# OpenPLCv0_2_0_SDCard.net
KiCad netlist of a schematic drawn in Altium Designer
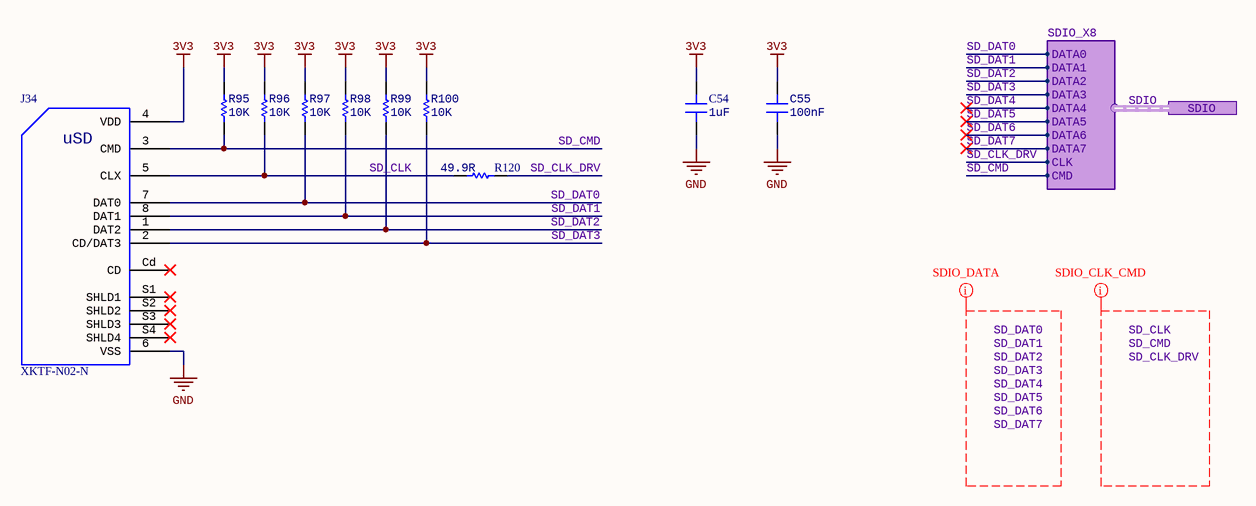
[diagram p0: OpenPLCv0.2.0_SDCard.SchDoc]

(export (version "E")
  (design (tool "Eeschema 10.0.6"))
  (components
    (comp (ref "C54")
      (value "CC0603KRX5R9BB105")
      (footprint "SMD_CAP_0603(0201)_N")
      (description "1uF ±10% 50V X5R 0603 Multilayer Ceramic Capacitors MLCC - SMD/SMT RoHS")
      (fields (field (name "TOLERANCE") "10%") (field (name "CAPACITANCE") "1uF"))
      (libsource (lib "BrauV2_Capacitor") (part "1uF 0603 50V 10%"))
    )
    (comp (ref "C55")
      (value "CC0402KRX5R6BB104")
      (footprint "SMD_CAP_0402(1005)_N")
      (description "100nF ±10% 10V X5R 0402 Multilayer Ceramic Capacitors MLCC - SMD/SMT RoHS")
      (fields (field (name "TOLERANCE") "10%") (field (name "CAPACITANCE") "100nF"))
      (libsource (lib "BrauV2_Capacitor") (part "100nF 0402 10V 10%"))
    )
    (comp (ref "J34")
      (value "XKTF-N02-N")
      (footprint "XKTF-N02-N")
      (description "XKB Enterprise XKTF-N02-N  \r\nSMD Card Sockets Connectors RoHS")
      (libsource (lib "BrauV2_Connector") (part "XKTF-N02-N"))
    )
    (comp (ref "R95")
      (value "RC0402FR-0710KL")
      (footprint "SMD_RES_0402(1005)_N")
      (description "10kΩ ±1% 1/16W ±100ppm/℃ 0402 Chip Resistor - Surface Mount RoHS")
      (fields (field (name "TOLERANCE") "1%") (field (name "RESISTANCE") "10K"))
      (libsource (lib "BrauV2_Resistor") (part "10K 0402 1% 1/16W"))
    )
    (comp (ref "R96")
      (value "RC0402FR-0710KL")
      (footprint "SMD_RES_0402(1005)_N")
      (description "10kΩ ±1% 1/16W ±100ppm/℃ 0402 Chip Resistor - Surface Mount RoHS")
      (fields (field (name "TOLERANCE") "1%") (field (name "RESISTANCE") "10K"))
      (libsource (lib "BrauV2_Resistor") (part "10K 0402 1% 1/16W"))
    )
    (comp (ref "R97")
      (value "RC0402FR-0710KL")
      (footprint "SMD_RES_0402(1005)_N")
      (description "10kΩ ±1% 1/16W ±100ppm/℃ 0402 Chip Resistor - Surface Mount RoHS")
      (fields (field (name "TOLERANCE") "1%") (field (name "RESISTANCE") "10K"))
      (libsource (lib "BrauV2_Resistor") (part "10K 0402 1% 1/16W"))
    )
    (comp (ref "R98")
      (value "RC0402FR-0710KL")
      (footprint "SMD_RES_0402(1005)_N")
      (description "10kΩ ±1% 1/16W ±100ppm/℃ 0402 Chip Resistor - Surface Mount RoHS")
      (fields (field (name "TOLERANCE") "1%") (field (name "RESISTANCE") "10K"))
      (libsource (lib "BrauV2_Resistor") (part "10K 0402 1% 1/16W"))
    )
    (comp (ref "R99")
      (value "RC0402FR-0710KL")
      (footprint "SMD_RES_0402(1005)_N")
      (description "10kΩ ±1% 1/16W ±100ppm/℃ 0402 Chip Resistor - Surface Mount RoHS")
      (fields (field (name "TOLERANCE") "1%") (field (name "RESISTANCE") "10K"))
      (libsource (lib "BrauV2_Resistor") (part "10K 0402 1% 1/16W"))
    )
    (comp (ref "R100")
      (value "RC0402FR-0710KL")
      (footprint "SMD_RES_0402(1005)_N")
      (description "10kΩ ±1% 1/16W ±100ppm/℃ 0402 Chip Resistor - Surface Mount RoHS")
      (fields (field (name "TOLERANCE") "1%") (field (name "RESISTANCE") "10K"))
      (libsource (lib "BrauV2_Resistor") (part "10K 0402 1% 1/16W"))
    )
    (comp (ref "R120")
      (value "RC0402FR-0749R9L")
      (footprint "SMD_RES_0402(1005)_N")
      (description "49.9Ω ±1% 1/16W ±100ppm/℃ 0402 Chip Resistor - Surface Mount RoHS")
      (fields (field (name "TOLERANCE") "1%") (field (name "RESISTANCE") "49.9R"))
      (libsource (lib "OpenPLCv0.2.0_Resistor") (part "49R9 0402 1% 1/16W"))
    )
  )
  (nets
    (net (code "3") (name "/SD_CLK") (class "Default")
      (node (ref "J34") (pin "5") (pinfunction "CLX_5") (pintype "passive"))
      (node (ref "R120") (pin "1") (pinfunction "1_1") (pintype "passive"))
      (node (ref "R96") (pin "1") (pinfunction "1_1") (pintype "passive"))
    )
    (net (code "4") (name "/SD_CLK_DRV") (class "Default")
      (node (ref "R120") (pin "2") (pinfunction "2_2") (pintype "passive"))
    )
    (net (code "5") (name "/SD_CMD") (class "Default")
      (node (ref "J34") (pin "3") (pinfunction "CMD_3") (pintype "passive"))
      (node (ref "R95") (pin "1") (pinfunction "1_1") (pintype "passive"))
    )
    (net (code "6") (name "/SD_DAT0") (class "Default")
      (node (ref "J34") (pin "7") (pinfunction "DAT0_7") (pintype "passive"))
      (node (ref "R97") (pin "1") (pinfunction "1_1") (pintype "passive"))
    )
    (net (code "7") (name "/SD_DAT1") (class "Default")
      (node (ref "J34") (pin "8") (pinfunction "DAT1_8") (pintype "passive"))
      (node (ref "R98") (pin "1") (pinfunction "1_1") (pintype "passive"))
    )
    (net (code "8") (name "/SD_DAT2") (class "Default")
      (node (ref "J34") (pin "1") (pinfunction "DAT2_1") (pintype "passive"))
      (node (ref "R99") (pin "1") (pinfunction "1_1") (pintype "passive"))
    )
    (net (code "9") (name "/SD_DAT3") (class "Default")
      (node (ref "J34") (pin "2") (pinfunction "CD/DAT3_2") (pintype "passive"))
      (node (ref "R100") (pin "1") (pinfunction "1_1") (pintype "passive"))
    )
    (net (code "14") (name "3V3") (class "Default")
      (node (ref "C54") (pin "2") (pinfunction "2_2") (pintype "passive"))
      (node (ref "C55") (pin "2") (pinfunction "2_2") (pintype "passive"))
      (node (ref "J34") (pin "4") (pinfunction "VDD_4") (pintype "passive"))
      (node (ref "R100") (pin "2") (pinfunction "2_2") (pintype "passive"))
      (node (ref "R95") (pin "2") (pinfunction "2_2") (pintype "passive"))
      (node (ref "R96") (pin "2") (pinfunction "2_2") (pintype "passive"))
      (node (ref "R97") (pin "2") (pinfunction "2_2") (pintype "passive"))
      (node (ref "R98") (pin "2") (pinfunction "2_2") (pintype "passive"))
      (node (ref "R99") (pin "2") (pinfunction "2_2") (pintype "passive"))
    )
    (net (code "15") (name "GND") (class "Default")
      (node (ref "C54") (pin "1") (pinfunction "1_1") (pintype "passive"))
      (node (ref "C55") (pin "1") (pinfunction "1_1") (pintype "passive"))
      (node (ref "J34") (pin "6") (pinfunction "VSS_6") (pintype "passive"))
    )
    (net (code "16") (name "unconnected-(J34-CD-PadCd)") (class "Default")
      (node (ref "J34") (pin "Cd") (pinfunction "CD_Cd") (pintype "passive+no_connect"))
    )
    (net (code "17") (name "unconnected-(J34-SHLD1-PadS1)") (class "Default")
      (node (ref "J34") (pin "S1") (pinfunction "SHLD1_S1") (pintype "passive+no_connect"))
    )
    (net (code "18") (name "unconnected-(J34-SHLD2-PadS2)") (class "Default")
      (node (ref "J34") (pin "S2") (pinfunction "SHLD2_S2") (pintype "passive+no_connect"))
    )
    (net (code "19") (name "unconnected-(J34-SHLD3-PadS3)") (class "Default")
      (node (ref "J34") (pin "S3") (pinfunction "SHLD3_S3") (pintype "passive+no_connect"))
    )
    (net (code "20") (name "unconnected-(J34-SHLD4-PadS4)") (class "Default")
      (node (ref "J34") (pin "S4") (pinfunction "SHLD4_S4") (pintype "passive+no_connect"))
    )
  )
)
